# L298N_Motor_Driver_Module_Schematic.net
KiCad netlist of a schematic drawn in Altium Designer
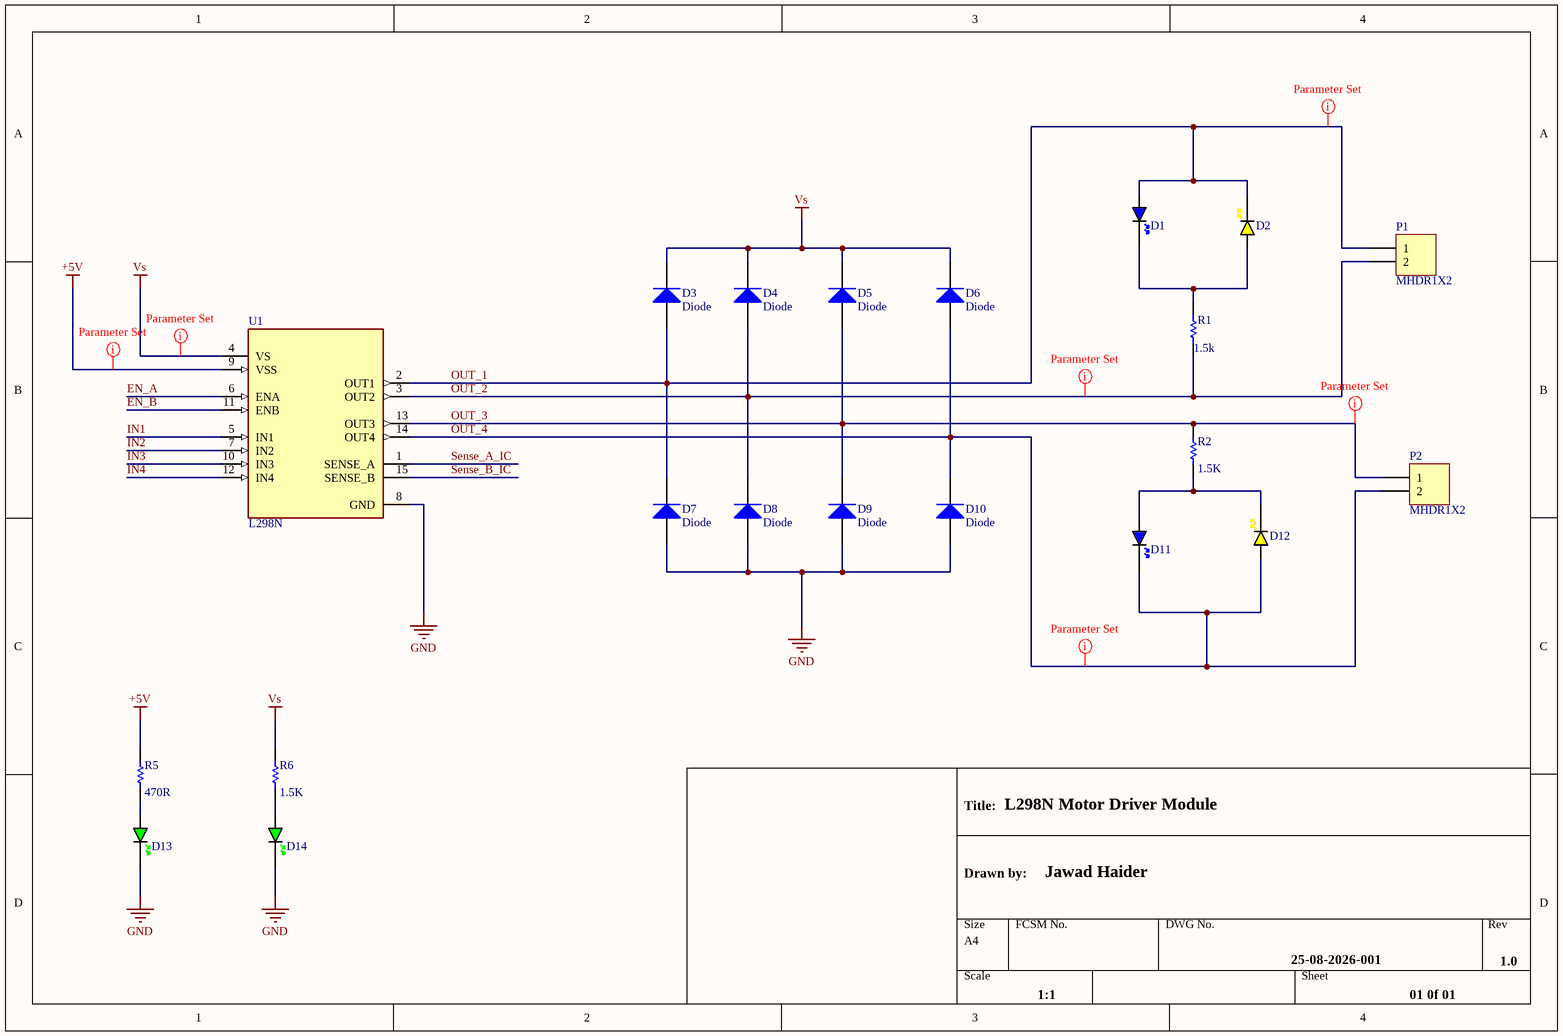
[diagram p0: L298N Motor Driver Module Schematic.SchDoc]

(export (version "E")
  (design (tool "Eeschema 10.0.6"))
  (components
    (comp (ref "D1")
      (value "BLUE")
      (footprint "LED_0603_BLUE")
      (description "LED 0603 BLUE SMD")
      (libsource (lib "Schematic-Lib-PhilsLab") (part "LED_0603_BLUE"))
    )
    (comp (ref "D2")
      (value "YELLOW")
      (footprint "LED_0603_YELLOW")
      (description "LED 0603 YELLOW SMD")
      (libsource (lib "Schematic-Lib-PhilsLab") (part "LED_0603_YELLOW"))
    )
    (comp (ref "D3")
      (value "Diode")
      (footprint "Diode_M7_SMA")
      (description "Default Diode")
      (fields (field (name "PUBLISHER") "Altium Limited"))
      (libsource (lib "Miscellaneous Devices") (part "Diode"))
    )
    (comp (ref "D4")
      (value "Diode")
      (footprint "Diode_M7_SMA")
      (description "Default Diode")
      (fields (field (name "PUBLISHER") "Altium Limited"))
      (libsource (lib "Miscellaneous Devices") (part "Diode"))
    )
    (comp (ref "D5")
      (value "Diode")
      (footprint "Diode_M7_SMA")
      (description "Default Diode")
      (fields (field (name "PUBLISHER") "Altium Limited"))
      (libsource (lib "Miscellaneous Devices") (part "Diode"))
    )
    (comp (ref "D6")
      (value "Diode")
      (footprint "Diode_M7_SMA")
      (description "Default Diode")
      (fields (field (name "PUBLISHER") "Altium Limited"))
      (libsource (lib "Miscellaneous Devices") (part "Diode"))
    )
    (comp (ref "D7")
      (value "Diode")
      (footprint "Diode_M7_SMA")
      (description "Default Diode")
      (fields (field (name "PUBLISHER") "Altium Limited"))
      (libsource (lib "Miscellaneous Devices") (part "Diode"))
    )
    (comp (ref "D8")
      (value "Diode")
      (footprint "Diode_M7_SMA")
      (description "Default Diode")
      (fields (field (name "PUBLISHER") "Altium Limited"))
      (libsource (lib "Miscellaneous Devices") (part "Diode"))
    )
    (comp (ref "D9")
      (value "Diode")
      (footprint "Diode_M7_SMA")
      (description "Default Diode")
      (fields (field (name "PUBLISHER") "Altium Limited"))
      (libsource (lib "Miscellaneous Devices") (part "Diode"))
    )
    (comp (ref "D10")
      (value "Diode")
      (footprint "Diode_M7_SMA")
      (description "Default Diode")
      (fields (field (name "PUBLISHER") "Altium Limited"))
      (libsource (lib "Miscellaneous Devices") (part "Diode"))
    )
    (comp (ref "D11")
      (value "BLUE")
      (footprint "LED_0603_BLUE")
      (description "LED 0603 BLUE SMD")
      (libsource (lib "Schematic-Lib-PhilsLab") (part "LED_0603_BLUE"))
    )
    (comp (ref "D12")
      (value "YELLOW")
      (footprint "LED_0603_YELLOW")
      (description "LED 0603 YELLOW SMD")
      (libsource (lib "Schematic-Lib-PhilsLab") (part "LED_0603_YELLOW"))
    )
    (comp (ref "D13")
      (value "GREEN")
      (footprint "LED_0603_GREEN")
      (description "LED 0603 GREEN SMD")
      (libsource (lib "Schematic-Lib-PhilsLab") (part "LED_0603_GREEN"))
    )
    (comp (ref "D14")
      (value "GREEN")
      (footprint "LED_0603_GREEN")
      (description "LED 0603 GREEN SMD")
      (libsource (lib "Schematic-Lib-PhilsLab") (part "LED_0603_GREEN"))
    )
    (comp (ref "P1")
      (value "MHDR1X2")
      (footprint "Terminal block 2 pin 5.08mm")
      (description "Header, 2-Pin")
      (fields (field (name "PUBLISHER") "Altium Limited"))
      (libsource (lib "Miscellaneous Connectors") (part "MHDR1X2"))
    )
    (comp (ref "P2")
      (value "MHDR1X2")
      (footprint "Terminal block 2 pin 5.08mm")
      (description "Header, 2-Pin")
      (fields (field (name "PUBLISHER") "Altium Limited"))
      (libsource (lib "Miscellaneous Connectors") (part "MHDR1X2"))
    )
    (comp (ref "R1")
      (value "1.5k")
      (footprint "RES_0603")
      (description "Resistor")
      (fields (field (name "Comment") "Res1") (field (name "PUBLISHER") "Altium Limited"))
      (libsource (lib "Miscellaneous Devices") (part "Res1"))
    )
    (comp (ref "R2")
      (value "1.5K")
      (footprint "RES_0603")
      (description "Resistor")
      (fields (field (name "Comment") "Res1") (field (name "PUBLISHER") "Altium Limited"))
      (libsource (lib "Miscellaneous Devices") (part "Res1"))
    )
    (comp (ref "R5")
      (value "470R")
      (footprint "RES_0603")
      (description "Resistor")
      (fields (field (name "Comment") "Res1") (field (name "PUBLISHER") "Altium Limited"))
      (libsource (lib "Miscellaneous Devices") (part "Res1"))
    )
    (comp (ref "R6")
      (value "1.5K")
      (footprint "RES_0603")
      (description "Resistor")
      (fields (field (name "Comment") "Res1") (field (name "PUBLISHER") "Altium Limited"))
      (libsource (lib "Miscellaneous Devices") (part "Res1"))
    )
    (comp (ref "U1")
      (value "L298N")
      (footprint "TO127P2020X500X2100-15")
      (description "Dual Full Bridge Motor Driver 15-Pin(15+Tab) MULTIWATT V Tube")
      (libsource (lib "L298N") (part "L298N"))
    )
  )
  (nets
    (net (code "1") (name "+5V") (class "Default")
      (node (ref "R5") (pin "2") (pinfunction "2_2") (pintype "passive"))
      (node (ref "U1") (pin "9") (pinfunction "VSS_9") (pintype "input"))
    )
    (net (code "2") (name "/EN_A") (class "Default")
      (node (ref "U1") (pin "6") (pinfunction "ENA_6") (pintype "input"))
    )
    (net (code "3") (name "/EN_B") (class "Default")
      (node (ref "U1") (pin "11") (pinfunction "ENB_11") (pintype "input"))
    )
    (net (code "4") (name "/IN1") (class "Default")
      (node (ref "U1") (pin "5") (pinfunction "IN1_5") (pintype "input"))
    )
    (net (code "5") (name "/IN2") (class "Default")
      (node (ref "U1") (pin "7") (pinfunction "IN2_7") (pintype "input"))
    )
    (net (code "6") (name "/IN3") (class "Default")
      (node (ref "U1") (pin "10") (pinfunction "IN3_10") (pintype "input"))
    )
    (net (code "7") (name "/IN4") (class "Default")
      (node (ref "U1") (pin "12") (pinfunction "IN4_12") (pintype "input"))
    )
    (net (code "8") (name "/OUT_1") (class "Default")
      (node (ref "D1") (pin "A") (pinfunction "A_A") (pintype "passive"))
      (node (ref "D2") (pin "K") (pinfunction "K_K") (pintype "passive"))
      (node (ref "D3") (pin "1") (pinfunction "A_1") (pintype "passive"))
      (node (ref "D7") (pin "2") (pinfunction "K_2") (pintype "passive"))
      (node (ref "P1") (pin "1") (pinfunction "1_1") (pintype "passive"))
      (node (ref "U1") (pin "2") (pinfunction "OUT1_2") (pintype "output"))
    )
    (net (code "9") (name "/OUT_2") (class "Default")
      (node (ref "D4") (pin "1") (pinfunction "A_1") (pintype "passive"))
      (node (ref "D8") (pin "2") (pinfunction "K_2") (pintype "passive"))
      (node (ref "P1") (pin "2") (pinfunction "2_2") (pintype "passive"))
      (node (ref "R1") (pin "1") (pinfunction "1_1") (pintype "passive"))
      (node (ref "U1") (pin "3") (pinfunction "OUT2_3") (pintype "output"))
    )
    (net (code "10") (name "/OUT_3") (class "Default")
      (node (ref "D5") (pin "1") (pinfunction "A_1") (pintype "passive"))
      (node (ref "D9") (pin "2") (pinfunction "K_2") (pintype "passive"))
      (node (ref "P2") (pin "1") (pinfunction "1_1") (pintype "passive"))
      (node (ref "R2") (pin "2") (pinfunction "2_2") (pintype "passive"))
      (node (ref "U1") (pin "13") (pinfunction "OUT3_13") (pintype "output"))
    )
    (net (code "11") (name "/OUT_4") (class "Default")
      (node (ref "D10") (pin "2") (pinfunction "K_2") (pintype "passive"))
      (node (ref "D11") (pin "K") (pinfunction "K_K") (pintype "passive"))
      (node (ref "D12") (pin "A") (pinfunction "A_A") (pintype "passive"))
      (node (ref "D6") (pin "1") (pinfunction "A_1") (pintype "passive"))
      (node (ref "P2") (pin "2") (pinfunction "2_2") (pintype "passive"))
      (node (ref "U1") (pin "14") (pinfunction "OUT4_14") (pintype "output"))
    )
    (net (code "12") (name "/Sense_A_IC") (class "Default")
      (node (ref "U1") (pin "1") (pinfunction "SENSE_A_1") (pintype "passive"))
    )
    (net (code "13") (name "/Sense_B_IC") (class "Default")
      (node (ref "U1") (pin "15") (pinfunction "SENSE_B_15") (pintype "passive"))
    )
    (net (code "14") (name "GND") (class "Default")
      (node (ref "D10") (pin "1") (pinfunction "A_1") (pintype "passive"))
      (node (ref "D13") (pin "K") (pinfunction "K_K") (pintype "passive"))
      (node (ref "D14") (pin "K") (pinfunction "K_K") (pintype "passive"))
      (node (ref "D7") (pin "1") (pinfunction "A_1") (pintype "passive"))
      (node (ref "D8") (pin "1") (pinfunction "A_1") (pintype "passive"))
      (node (ref "D9") (pin "1") (pinfunction "A_1") (pintype "passive"))
      (node (ref "U1") (pin "8") (pinfunction "GND_8") (pintype "power_in"))
    )
    (net (code "15") (name "Net-(D1-PadK)") (class "Default")
      (node (ref "D1") (pin "K") (pinfunction "K_K") (pintype "passive"))
      (node (ref "D2") (pin "A") (pinfunction "A_A") (pintype "passive"))
      (node (ref "R1") (pin "2") (pinfunction "2_2") (pintype "passive"))
    )
    (net (code "16") (name "Net-(D11-PadA)") (class "Default")
      (node (ref "D11") (pin "A") (pinfunction "A_A") (pintype "passive"))
      (node (ref "D12") (pin "K") (pinfunction "K_K") (pintype "passive"))
      (node (ref "R2") (pin "1") (pinfunction "1_1") (pintype "passive"))
    )
    (net (code "17") (name "Net-(D13-PadA)") (class "Default")
      (node (ref "D13") (pin "A") (pinfunction "A_A") (pintype "passive"))
      (node (ref "R5") (pin "1") (pinfunction "1_1") (pintype "passive"))
    )
    (net (code "18") (name "Net-(D14-PadA)") (class "Default")
      (node (ref "D14") (pin "A") (pinfunction "A_A") (pintype "passive"))
      (node (ref "R6") (pin "1") (pinfunction "1_1") (pintype "passive"))
    )
    (net (code "19") (name "Vs") (class "Default")
      (node (ref "D3") (pin "2") (pinfunction "K_2") (pintype "passive"))
      (node (ref "D4") (pin "2") (pinfunction "K_2") (pintype "passive"))
      (node (ref "D5") (pin "2") (pinfunction "K_2") (pintype "passive"))
      (node (ref "D6") (pin "2") (pinfunction "K_2") (pintype "passive"))
      (node (ref "R6") (pin "2") (pinfunction "2_2") (pintype "passive"))
      (node (ref "U1") (pin "4") (pinfunction "VS_4") (pintype "power_in"))
    )
  )
)
